# i2c_adc_avr.net
KiCad netlist of a schematic drawn in EAGLE
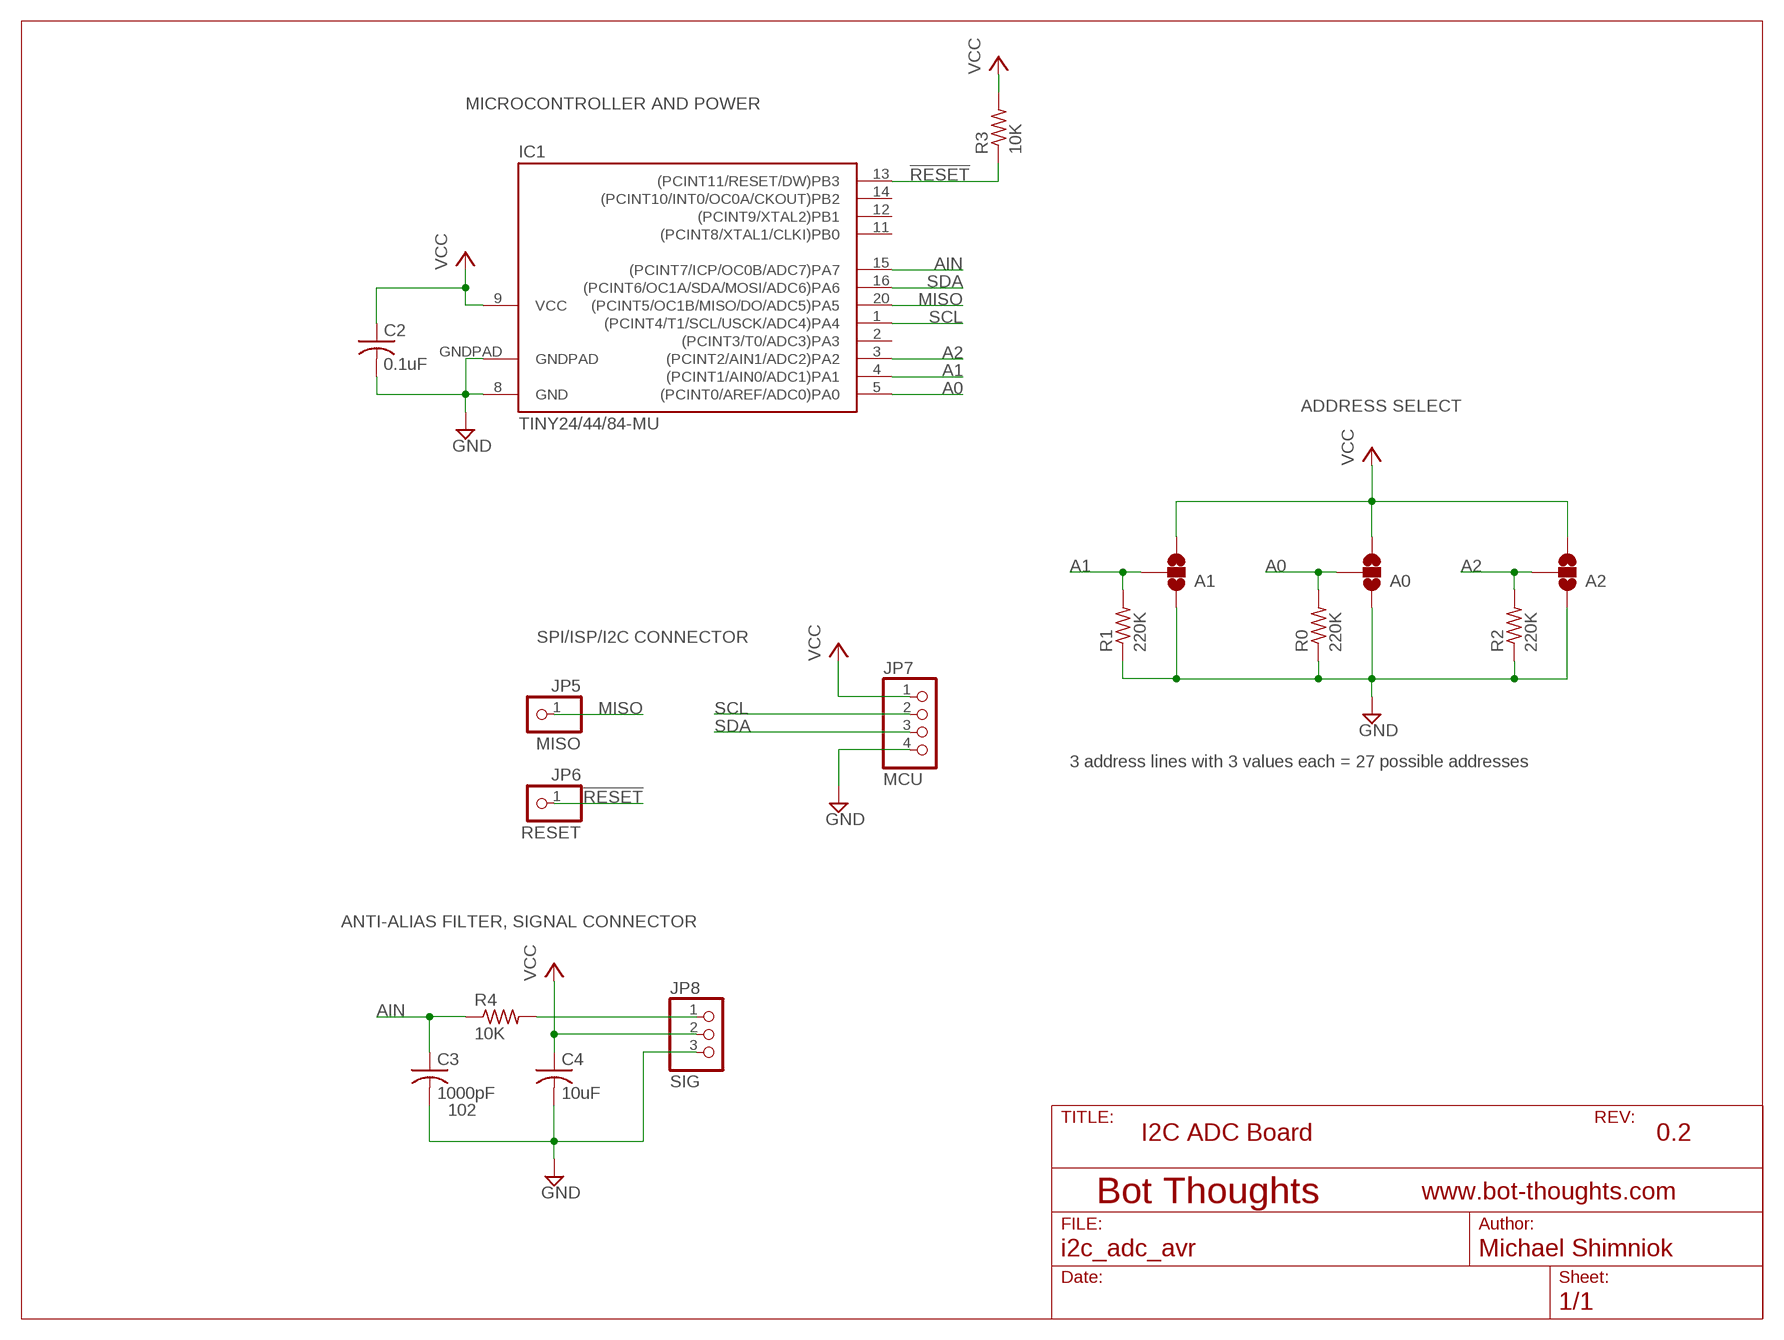
[diagram p0: schematic, sheet 1]

(export (version "E")
  (design (tool "Eeschema 10.0.6"))
  (components
    (comp (ref "A0")
      (value "SOLDERJUMPER_2WAYS")
      (footprint "eagle-import:SJ_3")
      (libsource (lib "eagle-import") (part "SOLDERJUMPER_2WAYS"))
    )
    (comp (ref "A1")
      (value "SOLDERJUMPER_2WAYS")
      (footprint "eagle-import:SJ_3")
      (libsource (lib "eagle-import") (part "SOLDERJUMPER_2WAYS"))
    )
    (comp (ref "A2")
      (value "SOLDERJUMPER_2WAYS")
      (footprint "eagle-import:SJ_3")
      (libsource (lib "eagle-import") (part "SOLDERJUMPER_2WAYS"))
    )
    (comp (ref "C2")
      (value "0.1uF")
      (footprint "eagle-import:C0603")
      (fields (field (name "PARTNO") "C1608X7R1E104K080AA"))
      (libsource (lib "eagle-import") (part "C-USC0603"))
    )
    (comp (ref "C3")
      (value "1000pF")
      (footprint "eagle-import:C0603")
      (fields (field (name "CODE") "102") (field (name "PARTNO") "CL10B102KB8SFNC"))
      (libsource (lib "eagle-import") (part "C-USC0603"))
    )
    (comp (ref "C4")
      (value "10uF")
      (footprint "eagle-import:C0603")
      (fields (field (name "PARTNO") "CL10A106MP8NNNC"))
      (libsource (lib "eagle-import") (part "C-USC0603"))
    )
    (comp (ref "IC1")
      (value "TINY24/44/84-MU")
      (footprint "eagle-import:QFN_MLF20")
      (fields (field (name "PARTNO") "ATTINY44A-MU"))
      (libsource (lib "eagle-import") (part "TINY24/44/84-MU"))
    )
    (comp (ref "JP5")
      (value "MISO")
      (footprint "eagle-import:1X01")
      (libsource (lib "eagle-import") (part "PINHD-1X01_2.54"))
    )
    (comp (ref "JP6")
      (value "RESET")
      (footprint "eagle-import:1X01")
      (libsource (lib "eagle-import") (part "PINHD-1X01_2.54"))
    )
    (comp (ref "JP7")
      (value "MCU")
      (footprint "eagle-import:1X04-S")
      (libsource (lib "eagle-import") (part "PINHD-1X04_2.54-S"))
    )
    (comp (ref "JP8")
      (value "SIG")
      (footprint "eagle-import:1X03M")
      (libsource (lib "eagle-import") (part "PINHD-1X03_2.00"))
    )
    (comp (ref "R0")
      (value "220K")
      (footprint "eagle-import:R0603")
      (fields (field (name "PARTNO") "RC1608J224CS"))
      (libsource (lib "eagle-import") (part "R-US_R0603"))
    )
    (comp (ref "R1")
      (value "220K")
      (footprint "eagle-import:R0603")
      (fields (field (name "PARTNO") "RC1608J224CS"))
      (libsource (lib "eagle-import") (part "R-US_R0603"))
    )
    (comp (ref "R2")
      (value "220K")
      (footprint "eagle-import:R0603")
      (fields (field (name "PARTNO") "RC1608J224CS"))
      (libsource (lib "eagle-import") (part "R-US_R0603"))
    )
    (comp (ref "R3")
      (value "10K")
      (footprint "eagle-import:R0603")
      (fields (field (name "PARTNO") "1622829-1"))
      (libsource (lib "eagle-import") (part "R-US_R0603"))
    )
    (comp (ref "R4")
      (value "10K")
      (footprint "eagle-import:R0603")
      (fields (field (name "PARTNO") "1622829-1"))
      (libsource (lib "eagle-import") (part "R-US_R0603"))
    )
  )
  (nets
    (net (code "1") (name "/A0") (class "Default")
      (node (ref "A0") (pin "2") (pinfunction "2_2") (pintype "passive"))
      (node (ref "IC1") (pin "5") (pinfunction "(PCINT0/AREF/ADC0)PA0_5") (pintype "bidirectional"))
      (node (ref "R0") (pin "2") (pinfunction "2_2") (pintype "passive"))
    )
    (net (code "2") (name "/A1") (class "Default")
      (node (ref "A1") (pin "2") (pinfunction "2_2") (pintype "passive"))
      (node (ref "IC1") (pin "4") (pinfunction "(PCINT1/AIN0/ADC1)PA1_4") (pintype "bidirectional"))
      (node (ref "R1") (pin "2") (pinfunction "2_2") (pintype "passive"))
    )
    (net (code "3") (name "/A2") (class "Default")
      (node (ref "A2") (pin "2") (pinfunction "2_2") (pintype "passive"))
      (node (ref "IC1") (pin "3") (pinfunction "(PCINT2/AIN1/ADC2)PA2_3") (pintype "bidirectional"))
      (node (ref "R2") (pin "2") (pinfunction "2_2") (pintype "passive"))
    )
    (net (code "4") (name "/AIN") (class "Default")
      (node (ref "C3") (pin "1") (pinfunction "1_1") (pintype "passive"))
      (node (ref "IC1") (pin "15") (pinfunction "(PCINT7/ICP/OC0B/ADC7)PA7_15") (pintype "bidirectional"))
      (node (ref "R4") (pin "1") (pinfunction "1_1") (pintype "passive"))
    )
    (net (code "5") (name "/MISO") (class "Default")
      (node (ref "IC1") (pin "20") (pinfunction "(PCINT5/OC1B/MISO/DO/ADC5)PA5_20") (pintype "bidirectional"))
      (node (ref "JP5") (pin "1") (pinfunction "1_1") (pintype "passive"))
    )
    (net (code "6") (name "/SCL") (class "Default")
      (node (ref "IC1") (pin "1") (pinfunction "(PCINT4/T1/SCL/USCK/ADC4)PA4_1") (pintype "bidirectional"))
      (node (ref "JP7") (pin "2") (pinfunction "2_2") (pintype "passive"))
    )
    (net (code "7") (name "/SDA") (class "Default")
      (node (ref "IC1") (pin "16") (pinfunction "(PCINT6/OC1A/SDA/MOSI/ADC6)PA6_16") (pintype "bidirectional"))
      (node (ref "JP7") (pin "3") (pinfunction "3_3") (pintype "passive"))
    )
    (net (code "8") (name "/~{RESET}") (class "Default")
      (node (ref "IC1") (pin "13") (pinfunction "(PCINT11/RESET/DW)PB3_13") (pintype "bidirectional"))
      (node (ref "JP6") (pin "1") (pinfunction "1_1") (pintype "passive"))
      (node (ref "R3") (pin "1") (pinfunction "1_1") (pintype "passive"))
    )
    (net (code "9") (name "GND") (class "Default")
      (node (ref "A0") (pin "1") (pinfunction "1_1") (pintype "passive"))
      (node (ref "A1") (pin "1") (pinfunction "1_1") (pintype "passive"))
      (node (ref "A2") (pin "1") (pinfunction "1_1") (pintype "passive"))
      (node (ref "C2") (pin "2") (pinfunction "2_2") (pintype "passive"))
      (node (ref "C3") (pin "2") (pinfunction "2_2") (pintype "passive"))
      (node (ref "C4") (pin "2") (pinfunction "2_2") (pintype "passive"))
      (node (ref "IC1") (pin "8") (pinfunction "GND_8") (pintype "power_in"))
      (node (ref "IC1") (pin "GNDPAD") (pinfunction "GNDPAD_GNDPAD") (pintype "power_in"))
      (node (ref "JP7") (pin "4") (pinfunction "4_4") (pintype "passive"))
      (node (ref "JP8") (pin "3") (pinfunction "3_3") (pintype "passive"))
      (node (ref "R0") (pin "1") (pinfunction "1_1") (pintype "passive"))
      (node (ref "R1") (pin "1") (pinfunction "1_1") (pintype "passive"))
      (node (ref "R2") (pin "1") (pinfunction "1_1") (pintype "passive"))
    )
    (net (code "10") (name "Net-(JP8-Pad1)") (class "Default")
      (node (ref "JP8") (pin "1") (pinfunction "1_1") (pintype "passive"))
      (node (ref "R4") (pin "2") (pinfunction "2_2") (pintype "passive"))
    )
    (net (code "11") (name "VCC") (class "Default")
      (node (ref "A0") (pin "3") (pinfunction "3_3") (pintype "passive"))
      (node (ref "A1") (pin "3") (pinfunction "3_3") (pintype "passive"))
      (node (ref "A2") (pin "3") (pinfunction "3_3") (pintype "passive"))
      (node (ref "C2") (pin "1") (pinfunction "1_1") (pintype "passive"))
      (node (ref "C4") (pin "1") (pinfunction "1_1") (pintype "passive"))
      (node (ref "IC1") (pin "9") (pinfunction "VCC_9") (pintype "power_in"))
      (node (ref "JP7") (pin "1") (pinfunction "1_1") (pintype "passive"))
      (node (ref "JP8") (pin "2") (pinfunction "2_2") (pintype "passive"))
      (node (ref "R3") (pin "2") (pinfunction "2_2") (pintype "passive"))
    )
    (net (code "12") (name "unconnected-(IC1-(PCINT3{slash}T0{slash}ADC3)PA3-Pad2)") (class "Default")
      (node (ref "IC1") (pin "2") (pinfunction "(PCINT3/T0/ADC3)PA3_2") (pintype "bidirectional"))
    )
    (net (code "13") (name "unconnected-(IC1-(PCINT8{slash}XTAL1{slash}CLKI)PB0-Pad11)") (class "Default")
      (node (ref "IC1") (pin "11") (pinfunction "(PCINT8/XTAL1/CLKI)PB0_11") (pintype "bidirectional"))
    )
    (net (code "14") (name "unconnected-(IC1-(PCINT9{slash}XTAL2)PB1-Pad12)") (class "Default")
      (node (ref "IC1") (pin "12") (pinfunction "(PCINT9/XTAL2)PB1_12") (pintype "bidirectional"))
    )
    (net (code "15") (name "unconnected-(IC1-(PCINT10{slash}INT0{slash}OC0A{slash}CKOUT)PB2-Pad14)") (class "Default")
      (node (ref "IC1") (pin "14") (pinfunction "(PCINT10/INT0/OC0A/CKOUT)PB2_14") (pintype "bidirectional"))
    )
  )
)
